# power_supply.net
KiCad netlist of a schematic drawn in Altium Designer
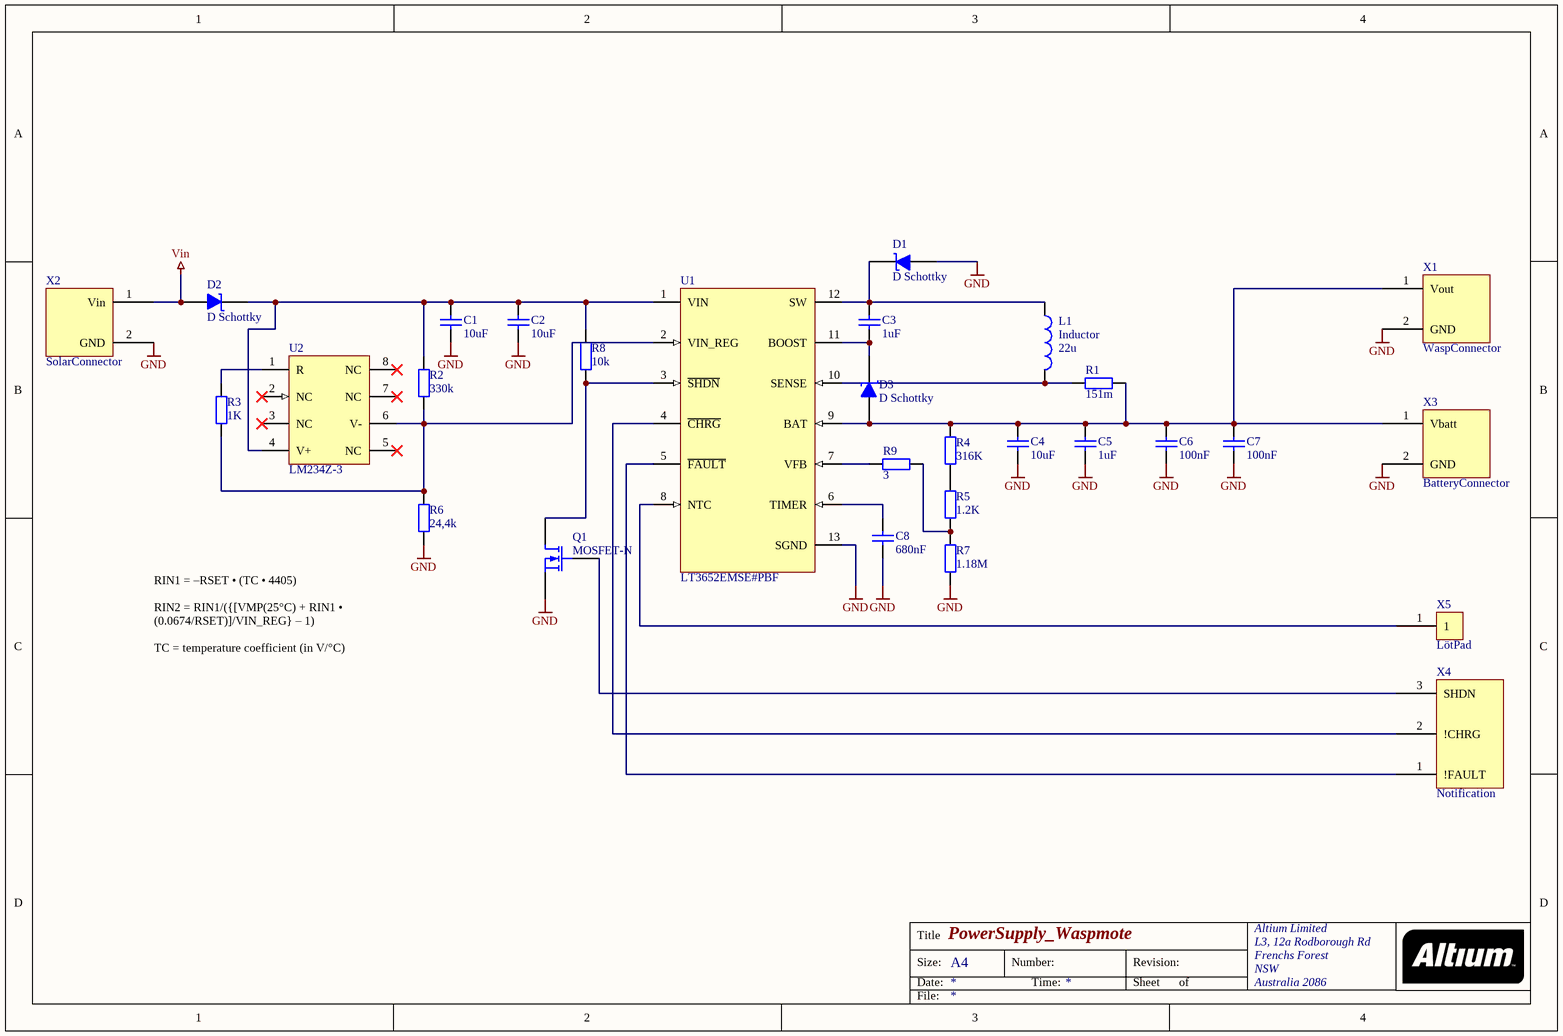
[diagram p0: power_supply.SchDoc]

(export (version "E")
  (design (tool "Eeschema 10.0.6"))
  (components
    (comp (ref "C1")
      (value "10uF")
      (footprint "C1210")
      (description "Capacitor")
      (fields (field (name "PUBLISHER") "Altium Limited"))
      (libsource (lib "Miscellaneous Devices") (part "Cap Semi"))
    )
    (comp (ref "C2")
      (value "10uF")
      (footprint "C1210")
      (description "Capacitor")
      (fields (field (name "PUBLISHER") "Altium Limited"))
      (libsource (lib "Miscellaneous Devices") (part "Cap Semi"))
    )
    (comp (ref "C3")
      (value "1uF")
      (footprint "C1210")
      (description "Capacitor")
      (fields (field (name "PUBLISHER") "Altium Limited"))
      (libsource (lib "Miscellaneous Devices") (part "Cap Semi"))
    )
    (comp (ref "C4")
      (value "10uF")
      (footprint "C1210")
      (description "Capacitor")
      (fields (field (name "PUBLISHER") "Altium Limited"))
      (libsource (lib "Miscellaneous Devices") (part "Cap Semi"))
    )
    (comp (ref "C5")
      (value "1uF")
      (footprint "C1210")
      (description "Capacitor")
      (fields (field (name "PUBLISHER") "Altium Limited"))
      (libsource (lib "Miscellaneous Devices") (part "Cap Semi"))
    )
    (comp (ref "C6")
      (value "100nF")
      (footprint "0402")
      (description "Capacitor")
      (fields (field (name "PUBLISHER") "Altium Limited"))
      (libsource (lib "Miscellaneous Devices") (part "Cap Semi"))
    )
    (comp (ref "C7")
      (value "100nF")
      (footprint "0402")
      (description "Capacitor")
      (fields (field (name "PUBLISHER") "Altium Limited"))
      (libsource (lib "Miscellaneous Devices") (part "Cap Semi"))
    )
    (comp (ref "C8")
      (value "680nF")
      (footprint "0402")
      (description "Capacitor")
      (fields (field (name "PUBLISHER") "Altium Limited"))
      (libsource (lib "Miscellaneous Devices") (part "Cap Semi"))
    )
    (comp (ref "D1")
      (value "D Schottky")
      (footprint "SMB")
      (description "Schottky Diode")
      (fields (field (name "PUBLISHER") "Altium Limited"))
      (libsource (lib "powerSupply") (part "D Schottky"))
    )
    (comp (ref "D2")
      (value "D Schottky")
      (footprint "SMB")
      (description "Schottky Diode")
      (fields (field (name "PUBLISHER") "Altium Limited"))
      (libsource (lib "powerSupply") (part "D Schottky"))
    )
    (comp (ref "D3")
      (value "D Schottky")
      (footprint "SMB")
      (description "Schottky Diode")
      (fields (field (name "PUBLISHER") "Altium Limited"))
      (libsource (lib "powerSupply") (part "D Schottky"))
    )
    (comp (ref "L1")
      (value "Inductor")
      (footprint "LMX131J")
      (fields (field (name "ALTIUM_VALUE") "22u"))
      (libsource (lib "Miscellaneous Devices") (part "Inductor"))
    )
    (comp (ref "Q1")
      (value "MOSFET-N")
      (footprint "Sot-23")
      (description "N-Channel MOSFET")
      (fields (field (name "PUBLISHER") "Altium Limited"))
      (libsource (lib "Miscellaneous Devices") (part "MOSFET-N"))
    )
    (comp (ref "R1")
      (value "151m")
      (footprint "2510")
      (description "Resistor")
      (fields (field (name "PUBLISHER") "Altium Limited"))
      (libsource (lib "") (part "Res2_1"))
    )
    (comp (ref "R2")
      (value "330k")
      (footprint "0603")
      (description "Resistor")
      (fields (field (name "PUBLISHER") "Altium Limited"))
      (libsource (lib "Miscellaneous Devices") (part "Res2"))
    )
    (comp (ref "R3")
      (value "1K")
      (footprint "0603")
      (description "Resistor")
      (fields (field (name "PUBLISHER") "Altium Limited"))
      (libsource (lib "Miscellaneous Devices") (part "Res2"))
    )
    (comp (ref "R4")
      (value "316K")
      (footprint "0603")
      (description "Resistor")
      (fields (field (name "PUBLISHER") "Altium Limited"))
      (libsource (lib "Miscellaneous Devices") (part "Res2"))
    )
    (comp (ref "R5")
      (value "1.2K")
      (footprint "0603")
      (description "Resistor")
      (fields (field (name "PUBLISHER") "Altium Limited"))
      (libsource (lib "Miscellaneous Devices") (part "Res2"))
    )
    (comp (ref "R6")
      (value "24,4k")
      (footprint "0603")
      (description "Resistor")
      (fields (field (name "PUBLISHER") "Altium Limited"))
      (libsource (lib "Miscellaneous Devices") (part "Res2"))
    )
    (comp (ref "R7")
      (value "1.18M")
      (footprint "0402")
      (description "Resistor")
      (fields (field (name "PUBLISHER") "Altium Limited"))
      (libsource (lib "Miscellaneous Devices") (part "Res2"))
    )
    (comp (ref "R8")
      (value "10k")
      (footprint "0603")
      (description "Resistor")
      (fields (field (name "PUBLISHER") "Altium Limited"))
      (libsource (lib "Miscellaneous Devices") (part "Res2"))
    )
    (comp (ref "R9")
      (value "3")
      (footprint "0402")
      (description "Resistor")
      (fields (field (name "PUBLISHER") "Altium Limited"))
      (libsource (lib "") (part "Res2_1"))
    )
    (comp (ref "U1")
      (value "LT3652EMSE#PBF")
      (footprint "LT-MSE-12-EDP_N")
      (description "Battery Charger for Solar Power")
      (fields (field (name "MANUFACTURER") "Linear Technology"))
      (libsource (lib "powerSupply") (part "LT3652EMSE#PBF"))
    )
    (comp (ref "U2")
      (value "LM234Z-3")
      (footprint "SO-8")
      (description "3-Terminal Adjustable Current Source, 3-pin TO-92")
      (fields (field (name "MANUFACTURER") "National Semiconductor"))
      (libsource (lib "PowerSupply_v1.1") (part "LM234Z-3"))
    )
    (comp (ref "X1")
      (value "WaspConnector")
      (footprint "Wasp_Connector")
      (description "Connector")
      (libsource (lib "powerSupply") (part "WaspConnector"))
    )
    (comp (ref "X2")
      (value "SolarConnector")
      (footprint "Solar_Connector")
      (description "Connector")
      (libsource (lib "powerSupply") (part "SolarConnector"))
    )
    (comp (ref "X3")
      (value "BatteryConnector")
      (footprint "Battery_Connector")
      (description "Connector")
      (libsource (lib "powerSupply") (part "BatteryConnector"))
    )
    (comp (ref "X4")
      (value "Notification")
      (footprint "NOTIFICATION_CONNECTOR")
      (description "Connector")
      (libsource (lib "PowerSupply_v1.1") (part "Notification"))
    )
    (comp (ref "X5")
      (value "LötPad")
      (footprint "LötPad")
      (description "PAD")
      (libsource (lib "PowerSupply_v1.1") (part "LötPad"))
    )
  )
  (nets
    (net (code "1") (name "GND") (class "Default")
      (node (ref "C1") (pin "1") (pinfunction "1_1") (pintype "passive"))
      (node (ref "C2") (pin "1") (pinfunction "1_1") (pintype "passive"))
      (node (ref "C4") (pin "1") (pinfunction "1_1") (pintype "passive"))
      (node (ref "C5") (pin "1") (pinfunction "1_1") (pintype "passive"))
      (node (ref "C6") (pin "1") (pinfunction "1_1") (pintype "passive"))
      (node (ref "C7") (pin "1") (pinfunction "1_1") (pintype "passive"))
      (node (ref "C8") (pin "1") (pinfunction "1_1") (pintype "passive"))
      (node (ref "D1") (pin "1") (pinfunction "A_1") (pintype "passive"))
      (node (ref "Q1") (pin "3") (pinfunction "S_3") (pintype "passive"))
      (node (ref "R6") (pin "1") (pinfunction "1_1") (pintype "passive"))
      (node (ref "R7") (pin "1") (pinfunction "1_1") (pintype "passive"))
      (node (ref "U1") (pin "13") (pinfunction "SGND_13") (pintype "power_in"))
      (node (ref "X1") (pin "2") (pinfunction "GND_2") (pintype "passive"))
      (node (ref "X2") (pin "2") (pinfunction "GND_2") (pintype "passive"))
      (node (ref "X3") (pin "2") (pinfunction "GND_2") (pintype "passive"))
    )
    (net (code "2") (name "Net-(D1-K)") (class "Default")
      (node (ref "C3") (pin "2") (pinfunction "2_2") (pintype "passive"))
      (node (ref "D1") (pin "2") (pinfunction "K_2") (pintype "passive"))
      (node (ref "L1") (pin "1") (pinfunction "1_1") (pintype "passive"))
      (node (ref "U1") (pin "12") (pinfunction "SW_12") (pintype "power_in"))
    )
    (net (code "3") (name "Net-(D2-K)") (class "Default")
      (node (ref "C1") (pin "2") (pinfunction "2_2") (pintype "passive"))
      (node (ref "C2") (pin "2") (pinfunction "2_2") (pintype "passive"))
      (node (ref "D2") (pin "2") (pinfunction "K_2") (pintype "passive"))
      (node (ref "R2") (pin "2") (pinfunction "2_2") (pintype "passive"))
      (node (ref "R8") (pin "2") (pinfunction "2_2") (pintype "passive"))
      (node (ref "U1") (pin "1") (pinfunction "VIN_1") (pintype "power_in"))
      (node (ref "U2") (pin "4") (pinfunction "V+_4") (pintype "passive"))
    )
    (net (code "4") (name "Net-(D3-A)") (class "Default")
      (node (ref "C4") (pin "2") (pinfunction "2_2") (pintype "passive"))
      (node (ref "C5") (pin "2") (pinfunction "2_2") (pintype "passive"))
      (node (ref "C6") (pin "2") (pinfunction "2_2") (pintype "passive"))
      (node (ref "C7") (pin "2") (pinfunction "2_2") (pintype "passive"))
      (node (ref "D3") (pin "1") (pinfunction "A_1") (pintype "passive"))
      (node (ref "R1") (pin "1") (pinfunction "1_1") (pintype "passive"))
      (node (ref "R4") (pin "2") (pinfunction "2_2") (pintype "passive"))
      (node (ref "U1") (pin "9") (pinfunction "BAT_9") (pintype "input"))
      (node (ref "X1") (pin "1") (pinfunction "Vout_1") (pintype "passive"))
      (node (ref "X3") (pin "1") (pinfunction "Vbatt_1") (pintype "passive"))
    )
    (net (code "5") (name "Net-(D3-K)") (class "Default")
      (node (ref "C3") (pin "1") (pinfunction "1_1") (pintype "passive"))
      (node (ref "D3") (pin "2") (pinfunction "K_2") (pintype "passive"))
      (node (ref "U1") (pin "11") (pinfunction "BOOST_11") (pintype "power_in"))
    )
    (net (code "6") (name "Net-(Q1-D)") (class "Default")
      (node (ref "Q1") (pin "1") (pinfunction "D_1") (pintype "passive"))
      (node (ref "R8") (pin "1") (pinfunction "1_1") (pintype "passive"))
      (node (ref "U1") (pin "3") (pinfunction "~{SHDN}_3") (pintype "input"))
    )
    (net (code "7") (name "Net-(Q1-G)") (class "Default")
      (node (ref "Q1") (pin "2") (pinfunction "G_2") (pintype "passive"))
      (node (ref "X4") (pin "3") (pinfunction "SHDN_3") (pintype "passive"))
    )
    (net (code "8") (name "Net-(R4-Pad1)") (class "Default")
      (node (ref "R4") (pin "1") (pinfunction "1_1") (pintype "passive"))
      (node (ref "R5") (pin "2") (pinfunction "2_2") (pintype "passive"))
    )
    (net (code "9") (name "Net-(R5-Pad1)") (class "Default")
      (node (ref "R5") (pin "1") (pinfunction "1_1") (pintype "passive"))
      (node (ref "R7") (pin "2") (pinfunction "2_2") (pintype "passive"))
      (node (ref "R9") (pin "1") (pinfunction "1_1") (pintype "passive"))
    )
    (net (code "10") (name "Net-(U1-NTC)") (class "Default")
      (node (ref "U1") (pin "8") (pinfunction "NTC_8") (pintype "input"))
      (node (ref "X5") (pin "1") (pinfunction "1_1") (pintype "passive"))
    )
    (net (code "11") (name "Net-(U1-SENSE)") (class "Default")
      (node (ref "L1") (pin "2") (pinfunction "2_2") (pintype "passive"))
      (node (ref "R1") (pin "2") (pinfunction "2_2") (pintype "passive"))
      (node (ref "U1") (pin "10") (pinfunction "SENSE_10") (pintype "input"))
    )
    (net (code "12") (name "Net-(U1-TIMER)") (class "Default")
      (node (ref "C8") (pin "2") (pinfunction "2_2") (pintype "passive"))
      (node (ref "U1") (pin "6") (pinfunction "TIMER_6") (pintype "input"))
    )
    (net (code "13") (name "Net-(U1-VFB)") (class "Default")
      (node (ref "R9") (pin "2") (pinfunction "2_2") (pintype "passive"))
      (node (ref "U1") (pin "7") (pinfunction "VFB_7") (pintype "input"))
    )
    (net (code "14") (name "Net-(U1-VIN_REG)") (class "Default")
      (node (ref "R2") (pin "1") (pinfunction "1_1") (pintype "passive"))
      (node (ref "R3") (pin "1") (pinfunction "1_1") (pintype "passive"))
      (node (ref "R6") (pin "2") (pinfunction "2_2") (pintype "passive"))
      (node (ref "U1") (pin "2") (pinfunction "VIN_REG_2") (pintype "input"))
      (node (ref "U2") (pin "6") (pinfunction "V-_6") (pintype "passive"))
    )
    (net (code "15") (name "Net-(U1-~{CHRG})") (class "Default")
      (node (ref "U1") (pin "4") (pinfunction "~{CHRG}_4") (pintype "tri_state"))
      (node (ref "X4") (pin "2") (pinfunction "!CHRG_2") (pintype "passive"))
    )
    (net (code "16") (name "Net-(U1-~{FAULT})") (class "Default")
      (node (ref "U1") (pin "5") (pinfunction "~{FAULT}_5") (pintype "tri_state"))
      (node (ref "X4") (pin "1") (pinfunction "!FAULT_1") (pintype "passive"))
    )
    (net (code "17") (name "Net-(U2-R)") (class "Default")
      (node (ref "R3") (pin "2") (pinfunction "2_2") (pintype "passive"))
      (node (ref "U2") (pin "1") (pinfunction "R_1") (pintype "passive"))
    )
    (net (code "18") (name "Vin") (class "Default")
      (node (ref "D2") (pin "1") (pinfunction "A_1") (pintype "passive"))
      (node (ref "X2") (pin "1") (pinfunction "Vin_1") (pintype "passive"))
    )
    (net (code "19") (name "unconnected-(U2-NC-Pad2)") (class "Default")
      (node (ref "U2") (pin "2") (pinfunction "NC_2") (pintype "input+no_connect"))
    )
    (net (code "20") (name "unconnected-(U2-NC-Pad3)") (class "Default")
      (node (ref "U2") (pin "3") (pinfunction "NC_3") (pintype "passive+no_connect"))
    )
    (net (code "21") (name "unconnected-(U2-NC-Pad5)") (class "Default")
      (node (ref "U2") (pin "5") (pinfunction "NC_5") (pintype "passive+no_connect"))
    )
    (net (code "22") (name "unconnected-(U2-NC-Pad7)") (class "Default")
      (node (ref "U2") (pin "7") (pinfunction "NC_7") (pintype "passive+no_connect"))
    )
    (net (code "23") (name "unconnected-(U2-NC-Pad8)") (class "Default")
      (node (ref "U2") (pin "8") (pinfunction "NC_8") (pintype "passive+no_connect"))
    )
  )
)
